# alu.net
KiCad netlist of a schematic drawn in EAGLE
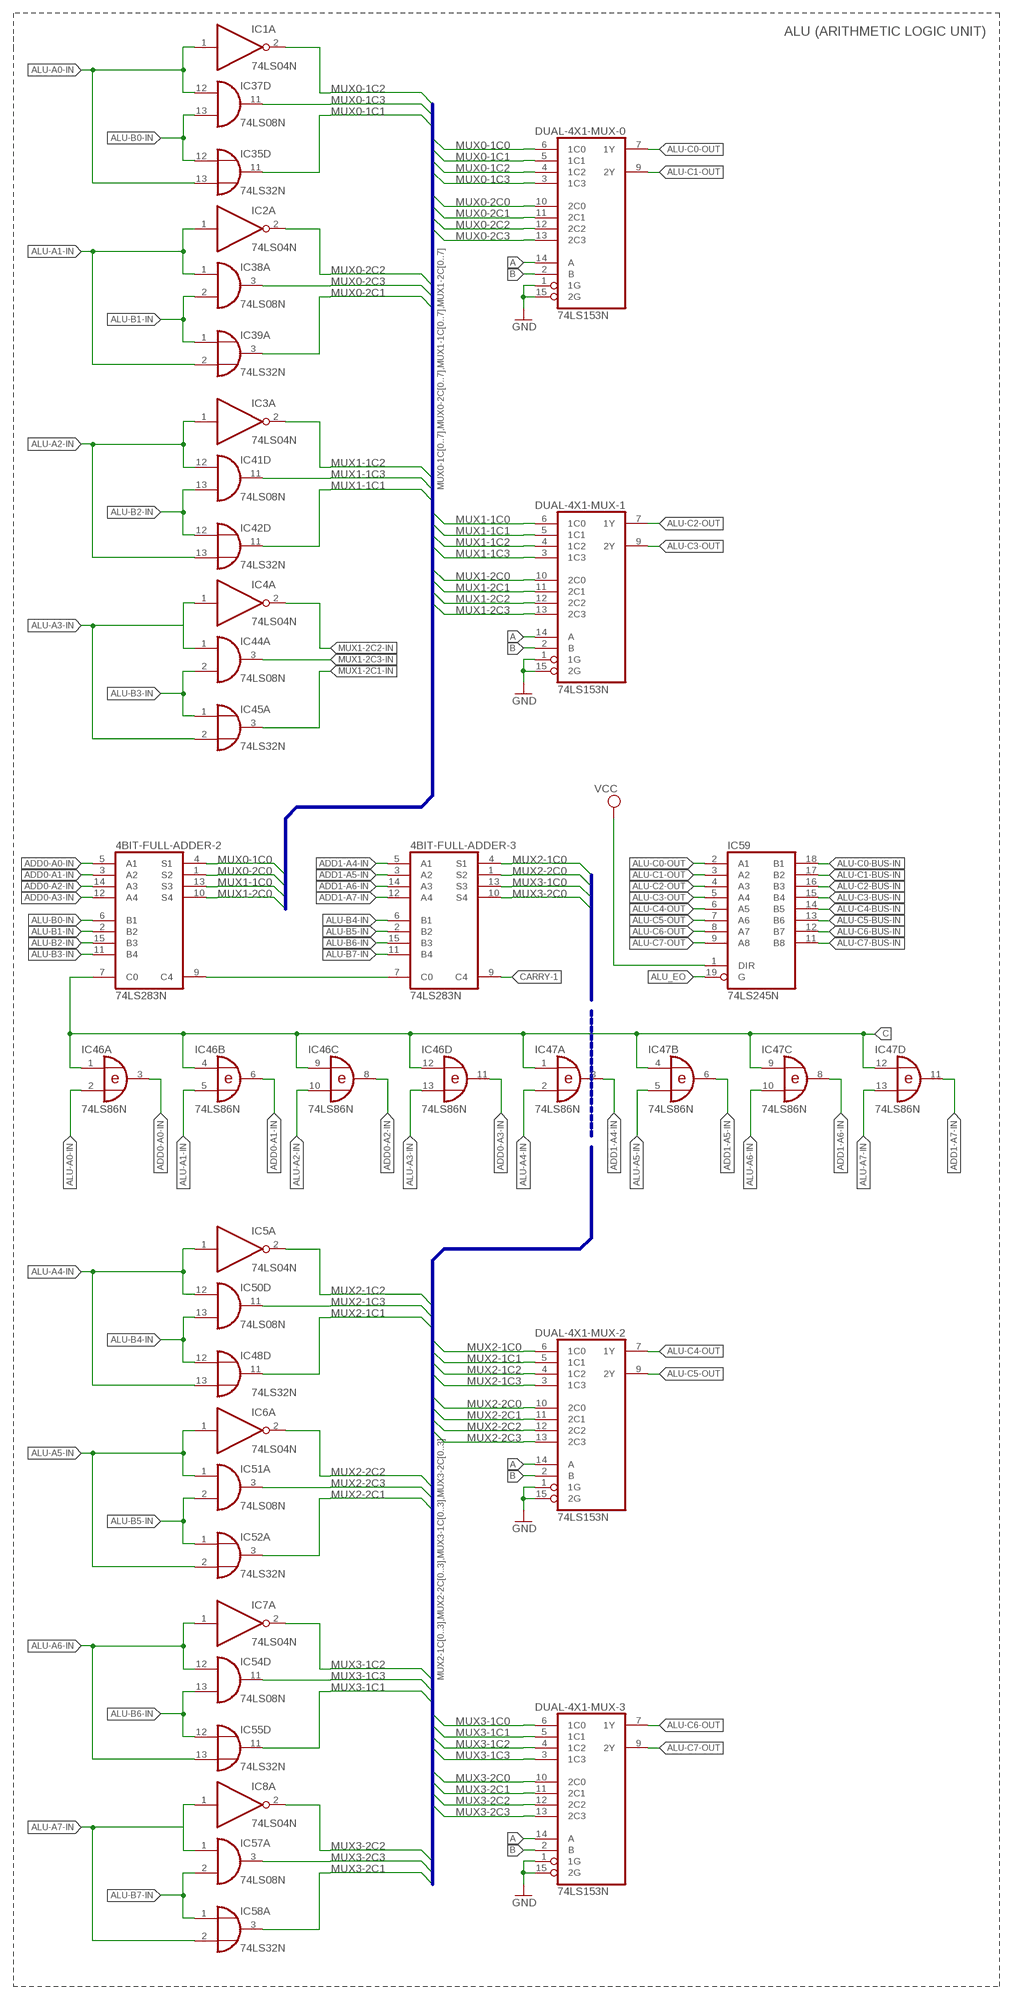
[diagram p0: schematic, sheet 1]

(export (version "E")
  (design (tool "Eeschema 10.0.6"))
  (components
    (comp (ref "4BIT-FULL-ADDER-2")
      (value "74LS283N")
      (footprint "eagle-import:DIL16")
      (libsource (lib "eagle-import") (part "74283NLS"))
    )
    (comp (ref "4BIT-FULL-ADDER-3")
      (value "74LS283N")
      (footprint "eagle-import:DIL16")
      (libsource (lib "eagle-import") (part "74283NLS"))
    )
    (comp (ref "DUAL-4X1-MUX-0")
      (value "74LS153N")
      (footprint "eagle-import:DIL16")
      (libsource (lib "eagle-import") (part "74153NLS"))
    )
    (comp (ref "DUAL-4X1-MUX-1")
      (value "74LS153N")
      (footprint "eagle-import:DIL16")
      (libsource (lib "eagle-import") (part "74153NLS"))
    )
    (comp (ref "DUAL-4X1-MUX-2")
      (value "74LS153N")
      (footprint "eagle-import:DIL16")
      (libsource (lib "eagle-import") (part "74153NLS"))
    )
    (comp (ref "DUAL-4X1-MUX-3")
      (value "74LS153N")
      (footprint "eagle-import:DIL16")
      (libsource (lib "eagle-import") (part "74153NLS"))
    )
    (comp (ref "IC1")
      (value "74LS04N")
      (footprint "eagle-import:DIL14")
      (libsource (lib "eagle-import") (part "7404NLS"))
    )
    (comp (ref "IC2")
      (value "74LS04N")
      (footprint "eagle-import:DIL14")
      (libsource (lib "eagle-import") (part "7404NLS"))
    )
    (comp (ref "IC3")
      (value "74LS04N")
      (footprint "eagle-import:DIL14")
      (libsource (lib "eagle-import") (part "7404NLS"))
    )
    (comp (ref "IC4")
      (value "74LS04N")
      (footprint "eagle-import:DIL14")
      (libsource (lib "eagle-import") (part "7404NLS"))
    )
    (comp (ref "IC5")
      (value "74LS04N")
      (footprint "eagle-import:DIL14")
      (libsource (lib "eagle-import") (part "7404NLS"))
    )
    (comp (ref "IC6")
      (value "74LS04N")
      (footprint "eagle-import:DIL14")
      (libsource (lib "eagle-import") (part "7404NLS"))
    )
    (comp (ref "IC7")
      (value "74LS04N")
      (footprint "eagle-import:DIL14")
      (libsource (lib "eagle-import") (part "7404NLS"))
    )
    (comp (ref "IC8")
      (value "74LS04N")
      (footprint "eagle-import:DIL14")
      (libsource (lib "eagle-import") (part "7404NLS"))
    )
    (comp (ref "IC35")
      (value "74LS32N")
      (footprint "eagle-import:DIL14")
      (libsource (lib "eagle-import") (part "7432NLS"))
    )
    (comp (ref "IC37")
      (value "74LS08N")
      (footprint "eagle-import:DIL14")
      (libsource (lib "eagle-import") (part "7408NLS"))
    )
    (comp (ref "IC38")
      (value "74LS08N")
      (footprint "eagle-import:DIL14")
      (libsource (lib "eagle-import") (part "7408NLS"))
    )
    (comp (ref "IC39")
      (value "74LS32N")
      (footprint "eagle-import:DIL14")
      (libsource (lib "eagle-import") (part "7432NLS"))
    )
    (comp (ref "IC41")
      (value "74LS08N")
      (footprint "eagle-import:DIL14")
      (libsource (lib "eagle-import") (part "7408NLS"))
    )
    (comp (ref "IC42")
      (value "74LS32N")
      (footprint "eagle-import:DIL14")
      (libsource (lib "eagle-import") (part "7432NLS"))
    )
    (comp (ref "IC44")
      (value "74LS08N")
      (footprint "eagle-import:DIL14")
      (libsource (lib "eagle-import") (part "7408NLS"))
    )
    (comp (ref "IC45")
      (value "74LS32N")
      (footprint "eagle-import:DIL14")
      (libsource (lib "eagle-import") (part "7432NLS"))
    )
    (comp (ref "IC46")
      (value "74LS86N")
      (footprint "eagle-import:DIL14")
      (libsource (lib "eagle-import") (part "7486NLS"))
    )
    (comp (ref "IC47")
      (value "74LS86N")
      (footprint "eagle-import:DIL14")
      (libsource (lib "eagle-import") (part "7486NLS"))
    )
    (comp (ref "IC48")
      (value "74LS32N")
      (footprint "eagle-import:DIL14")
      (libsource (lib "eagle-import") (part "7432NLS"))
    )
    (comp (ref "IC50")
      (value "74LS08N")
      (footprint "eagle-import:DIL14")
      (libsource (lib "eagle-import") (part "7408NLS"))
    )
    (comp (ref "IC51")
      (value "74LS08N")
      (footprint "eagle-import:DIL14")
      (libsource (lib "eagle-import") (part "7408NLS"))
    )
    (comp (ref "IC52")
      (value "74LS32N")
      (footprint "eagle-import:DIL14")
      (libsource (lib "eagle-import") (part "7432NLS"))
    )
    (comp (ref "IC54")
      (value "74LS08N")
      (footprint "eagle-import:DIL14")
      (libsource (lib "eagle-import") (part "7408NLS"))
    )
    (comp (ref "IC55")
      (value "74LS32N")
      (footprint "eagle-import:DIL14")
      (libsource (lib "eagle-import") (part "7432NLS"))
    )
    (comp (ref "IC57")
      (value "74LS08N")
      (footprint "eagle-import:DIL14")
      (libsource (lib "eagle-import") (part "7408NLS"))
    )
    (comp (ref "IC58")
      (value "74LS32N")
      (footprint "eagle-import:DIL14")
      (libsource (lib "eagle-import") (part "7432NLS"))
    )
    (comp (ref "IC59")
      (value "74LS245N")
      (footprint "eagle-import:DIL20")
      (libsource (lib "eagle-import") (part "74245NLS"))
    )
  )
  (nets
    (net (code "1") (name "/MUX0-1C0") (class "Default")
      (node (ref "4BIT-FULL-ADDER-2") (pin "4") (pinfunction "S1_4") (pintype "output"))
      (node (ref "DUAL-4X1-MUX-0") (pin "6") (pinfunction "1C0_6") (pintype "input"))
    )
    (net (code "2") (name "/MUX0-1C1") (class "Default")
      (node (ref "DUAL-4X1-MUX-0") (pin "5") (pinfunction "1C1_5") (pintype "input"))
      (node (ref "IC35") (pin "11") (pinfunction "O_11") (pintype "output"))
    )
    (net (code "3") (name "/MUX0-1C2") (class "Default")
      (node (ref "DUAL-4X1-MUX-0") (pin "4") (pinfunction "1C2_4") (pintype "input"))
      (node (ref "IC1") (pin "2") (pinfunction "O_2") (pintype "output"))
    )
    (net (code "4") (name "/MUX0-1C3") (class "Default")
      (node (ref "DUAL-4X1-MUX-0") (pin "3") (pinfunction "1C3_3") (pintype "input"))
      (node (ref "IC37") (pin "11") (pinfunction "O_11") (pintype "output"))
    )
    (net (code "5") (name "/MUX0-2C0") (class "Default")
      (node (ref "4BIT-FULL-ADDER-2") (pin "1") (pinfunction "S2_1") (pintype "output"))
      (node (ref "DUAL-4X1-MUX-0") (pin "10") (pinfunction "2C0_10") (pintype "input"))
    )
    (net (code "6") (name "/MUX0-2C1") (class "Default")
      (node (ref "DUAL-4X1-MUX-0") (pin "11") (pinfunction "2C1_11") (pintype "input"))
      (node (ref "IC39") (pin "3") (pinfunction "O_3") (pintype "output"))
    )
    (net (code "7") (name "/MUX0-2C2") (class "Default")
      (node (ref "DUAL-4X1-MUX-0") (pin "12") (pinfunction "2C2_12") (pintype "input"))
      (node (ref "IC2") (pin "2") (pinfunction "O_2") (pintype "output"))
    )
    (net (code "8") (name "/MUX0-2C3") (class "Default")
      (node (ref "DUAL-4X1-MUX-0") (pin "13") (pinfunction "2C3_13") (pintype "input"))
      (node (ref "IC38") (pin "3") (pinfunction "O_3") (pintype "output"))
    )
    (net (code "9") (name "/MUX1-1C0") (class "Default")
      (node (ref "4BIT-FULL-ADDER-2") (pin "13") (pinfunction "S3_13") (pintype "output"))
      (node (ref "DUAL-4X1-MUX-1") (pin "6") (pinfunction "1C0_6") (pintype "input"))
    )
    (net (code "10") (name "/MUX1-1C1") (class "Default")
      (node (ref "DUAL-4X1-MUX-1") (pin "5") (pinfunction "1C1_5") (pintype "input"))
      (node (ref "IC42") (pin "11") (pinfunction "O_11") (pintype "output"))
    )
    (net (code "11") (name "/MUX1-1C2") (class "Default")
      (node (ref "DUAL-4X1-MUX-1") (pin "4") (pinfunction "1C2_4") (pintype "input"))
      (node (ref "IC3") (pin "2") (pinfunction "O_2") (pintype "output"))
    )
    (net (code "12") (name "/MUX1-1C3") (class "Default")
      (node (ref "DUAL-4X1-MUX-1") (pin "3") (pinfunction "1C3_3") (pintype "input"))
      (node (ref "IC41") (pin "11") (pinfunction "O_11") (pintype "output"))
    )
    (net (code "13") (name "/MUX1-2C0") (class "Default")
      (node (ref "4BIT-FULL-ADDER-2") (pin "10") (pinfunction "S4_10") (pintype "output"))
      (node (ref "DUAL-4X1-MUX-1") (pin "10") (pinfunction "2C0_10") (pintype "input"))
    )
    (net (code "14") (name "/MUX1-2C1") (class "Default")
      (node (ref "DUAL-4X1-MUX-1") (pin "11") (pinfunction "2C1_11") (pintype "input"))
    )
    (net (code "15") (name "/MUX1-2C2") (class "Default")
      (node (ref "DUAL-4X1-MUX-1") (pin "12") (pinfunction "2C2_12") (pintype "input"))
    )
    (net (code "16") (name "/MUX1-2C3") (class "Default")
      (node (ref "DUAL-4X1-MUX-1") (pin "13") (pinfunction "2C3_13") (pintype "input"))
    )
    (net (code "17") (name "/MUX2-1C0") (class "Default")
      (node (ref "4BIT-FULL-ADDER-3") (pin "4") (pinfunction "S1_4") (pintype "output"))
      (node (ref "DUAL-4X1-MUX-2") (pin "6") (pinfunction "1C0_6") (pintype "input"))
    )
    (net (code "18") (name "/MUX2-1C1") (class "Default")
      (node (ref "DUAL-4X1-MUX-2") (pin "5") (pinfunction "1C1_5") (pintype "input"))
      (node (ref "IC48") (pin "11") (pinfunction "O_11") (pintype "output"))
    )
    (net (code "19") (name "/MUX2-1C2") (class "Default")
      (node (ref "DUAL-4X1-MUX-2") (pin "4") (pinfunction "1C2_4") (pintype "input"))
      (node (ref "IC5") (pin "2") (pinfunction "O_2") (pintype "output"))
    )
    (net (code "20") (name "/MUX2-1C3") (class "Default")
      (node (ref "DUAL-4X1-MUX-2") (pin "3") (pinfunction "1C3_3") (pintype "input"))
      (node (ref "IC50") (pin "11") (pinfunction "O_11") (pintype "output"))
    )
    (net (code "21") (name "/MUX2-2C0") (class "Default")
      (node (ref "4BIT-FULL-ADDER-3") (pin "1") (pinfunction "S2_1") (pintype "output"))
      (node (ref "DUAL-4X1-MUX-2") (pin "10") (pinfunction "2C0_10") (pintype "input"))
    )
    (net (code "22") (name "/MUX2-2C1") (class "Default")
      (node (ref "DUAL-4X1-MUX-2") (pin "11") (pinfunction "2C1_11") (pintype "input"))
      (node (ref "IC52") (pin "3") (pinfunction "O_3") (pintype "output"))
    )
    (net (code "23") (name "/MUX2-2C2") (class "Default")
      (node (ref "DUAL-4X1-MUX-2") (pin "12") (pinfunction "2C2_12") (pintype "input"))
      (node (ref "IC6") (pin "2") (pinfunction "O_2") (pintype "output"))
    )
    (net (code "24") (name "/MUX2-2C3") (class "Default")
      (node (ref "DUAL-4X1-MUX-2") (pin "13") (pinfunction "2C3_13") (pintype "input"))
      (node (ref "IC51") (pin "3") (pinfunction "O_3") (pintype "output"))
    )
    (net (code "25") (name "/MUX3-1C0") (class "Default")
      (node (ref "4BIT-FULL-ADDER-3") (pin "13") (pinfunction "S3_13") (pintype "output"))
      (node (ref "DUAL-4X1-MUX-3") (pin "6") (pinfunction "1C0_6") (pintype "input"))
    )
    (net (code "26") (name "/MUX3-1C1") (class "Default")
      (node (ref "DUAL-4X1-MUX-3") (pin "5") (pinfunction "1C1_5") (pintype "input"))
      (node (ref "IC55") (pin "11") (pinfunction "O_11") (pintype "output"))
    )
    (net (code "27") (name "/MUX3-1C2") (class "Default")
      (node (ref "DUAL-4X1-MUX-3") (pin "4") (pinfunction "1C2_4") (pintype "input"))
      (node (ref "IC7") (pin "2") (pinfunction "O_2") (pintype "output"))
    )
    (net (code "28") (name "/MUX3-1C3") (class "Default")
      (node (ref "DUAL-4X1-MUX-3") (pin "3") (pinfunction "1C3_3") (pintype "input"))
      (node (ref "IC54") (pin "11") (pinfunction "O_11") (pintype "output"))
    )
    (net (code "29") (name "/MUX3-2C0") (class "Default")
      (node (ref "4BIT-FULL-ADDER-3") (pin "10") (pinfunction "S4_10") (pintype "output"))
      (node (ref "DUAL-4X1-MUX-3") (pin "10") (pinfunction "2C0_10") (pintype "input"))
    )
    (net (code "30") (name "/MUX3-2C1") (class "Default")
      (node (ref "DUAL-4X1-MUX-3") (pin "11") (pinfunction "2C1_11") (pintype "input"))
      (node (ref "IC58") (pin "3") (pinfunction "O_3") (pintype "output"))
    )
    (net (code "31") (name "/MUX3-2C2") (class "Default")
      (node (ref "DUAL-4X1-MUX-3") (pin "12") (pinfunction "2C2_12") (pintype "input"))
      (node (ref "IC8") (pin "2") (pinfunction "O_2") (pintype "output"))
    )
    (net (code "32") (name "/MUX3-2C3") (class "Default")
      (node (ref "DUAL-4X1-MUX-3") (pin "13") (pinfunction "2C3_13") (pintype "input"))
      (node (ref "IC57") (pin "3") (pinfunction "O_3") (pintype "output"))
    )
    (net (code "35") (name "A") (class "Default")
      (node (ref "DUAL-4X1-MUX-0") (pin "14") (pinfunction "A_14") (pintype "input"))
      (node (ref "DUAL-4X1-MUX-1") (pin "14") (pinfunction "A_14") (pintype "input"))
      (node (ref "DUAL-4X1-MUX-2") (pin "14") (pinfunction "A_14") (pintype "input"))
      (node (ref "DUAL-4X1-MUX-3") (pin "14") (pinfunction "A_14") (pintype "input"))
    )
    (net (code "36") (name "ADD0-A0-IN") (class "Default")
      (node (ref "4BIT-FULL-ADDER-2") (pin "5") (pinfunction "A1_5") (pintype "input"))
      (node (ref "IC46") (pin "3") (pinfunction "O_3") (pintype "output"))
    )
    (net (code "37") (name "ADD0-A1-IN") (class "Default")
      (node (ref "4BIT-FULL-ADDER-2") (pin "3") (pinfunction "A2_3") (pintype "input"))
      (node (ref "IC46") (pin "6") (pinfunction "O_6") (pintype "output"))
    )
    (net (code "38") (name "ADD0-A2-IN") (class "Default")
      (node (ref "4BIT-FULL-ADDER-2") (pin "14") (pinfunction "A3_14") (pintype "input"))
      (node (ref "IC46") (pin "8") (pinfunction "O_8") (pintype "output"))
    )
    (net (code "39") (name "ADD0-A3-IN") (class "Default")
      (node (ref "4BIT-FULL-ADDER-2") (pin "12") (pinfunction "A4_12") (pintype "input"))
      (node (ref "IC46") (pin "11") (pinfunction "O_11") (pintype "output"))
    )
    (net (code "40") (name "ADD1-A4-IN") (class "Default")
      (node (ref "4BIT-FULL-ADDER-3") (pin "5") (pinfunction "A1_5") (pintype "input"))
      (node (ref "IC47") (pin "3") (pinfunction "O_3") (pintype "output"))
    )
    (net (code "41") (name "ADD1-A5-IN") (class "Default")
      (node (ref "4BIT-FULL-ADDER-3") (pin "3") (pinfunction "A2_3") (pintype "input"))
      (node (ref "IC47") (pin "6") (pinfunction "O_6") (pintype "output"))
    )
    (net (code "42") (name "ADD1-A6-IN") (class "Default")
      (node (ref "4BIT-FULL-ADDER-3") (pin "14") (pinfunction "A3_14") (pintype "input"))
      (node (ref "IC47") (pin "8") (pinfunction "O_8") (pintype "output"))
    )
    (net (code "43") (name "ADD1-A7-IN") (class "Default")
      (node (ref "4BIT-FULL-ADDER-3") (pin "12") (pinfunction "A4_12") (pintype "input"))
      (node (ref "IC47") (pin "11") (pinfunction "O_11") (pintype "output"))
    )
    (net (code "44") (name "ALU-A0-IN") (class "Default")
      (node (ref "IC1") (pin "1") (pinfunction "I_1") (pintype "input"))
      (node (ref "IC35") (pin "13") (pinfunction "I1_13") (pintype "input"))
      (node (ref "IC37") (pin "12") (pinfunction "I0_12") (pintype "input"))
      (node (ref "IC46") (pin "2") (pinfunction "I1_2") (pintype "input"))
    )
    (net (code "45") (name "ALU-A1-IN") (class "Default")
      (node (ref "IC2") (pin "1") (pinfunction "I_1") (pintype "input"))
      (node (ref "IC38") (pin "1") (pinfunction "I0_1") (pintype "input"))
      (node (ref "IC39") (pin "2") (pinfunction "I1_2") (pintype "input"))
      (node (ref "IC46") (pin "5") (pinfunction "I1_5") (pintype "input"))
    )
    (net (code "46") (name "ALU-A2-IN") (class "Default")
      (node (ref "IC3") (pin "1") (pinfunction "I_1") (pintype "input"))
      (node (ref "IC41") (pin "12") (pinfunction "I0_12") (pintype "input"))
      (node (ref "IC42") (pin "13") (pinfunction "I1_13") (pintype "input"))
      (node (ref "IC46") (pin "10") (pinfunction "I1_10") (pintype "input"))
    )
    (net (code "47") (name "ALU-A3-IN") (class "Default")
      (node (ref "IC4") (pin "1") (pinfunction "I_1") (pintype "input"))
      (node (ref "IC44") (pin "1") (pinfunction "I0_1") (pintype "input"))
      (node (ref "IC45") (pin "2") (pinfunction "I1_2") (pintype "input"))
      (node (ref "IC46") (pin "13") (pinfunction "I1_13") (pintype "input"))
    )
    (net (code "48") (name "ALU-A4-IN") (class "Default")
      (node (ref "IC47") (pin "2") (pinfunction "I1_2") (pintype "input"))
      (node (ref "IC48") (pin "13") (pinfunction "I1_13") (pintype "input"))
      (node (ref "IC5") (pin "1") (pinfunction "I_1") (pintype "input"))
      (node (ref "IC50") (pin "12") (pinfunction "I0_12") (pintype "input"))
    )
    (net (code "49") (name "ALU-A5-IN") (class "Default")
      (node (ref "IC47") (pin "5") (pinfunction "I1_5") (pintype "input"))
      (node (ref "IC51") (pin "1") (pinfunction "I0_1") (pintype "input"))
      (node (ref "IC52") (pin "2") (pinfunction "I1_2") (pintype "input"))
      (node (ref "IC6") (pin "1") (pinfunction "I_1") (pintype "input"))
    )
    (net (code "50") (name "ALU-A6-IN") (class "Default")
      (node (ref "IC47") (pin "10") (pinfunction "I1_10") (pintype "input"))
      (node (ref "IC54") (pin "12") (pinfunction "I0_12") (pintype "input"))
      (node (ref "IC55") (pin "13") (pinfunction "I1_13") (pintype "input"))
      (node (ref "IC7") (pin "1") (pinfunction "I_1") (pintype "input"))
    )
    (net (code "51") (name "ALU-A7-IN") (class "Default")
      (node (ref "IC47") (pin "13") (pinfunction "I1_13") (pintype "input"))
      (node (ref "IC57") (pin "1") (pinfunction "I0_1") (pintype "input"))
      (node (ref "IC58") (pin "2") (pinfunction "I1_2") (pintype "input"))
      (node (ref "IC8") (pin "1") (pinfunction "I_1") (pintype "input"))
    )
    (net (code "52") (name "ALU-B0-IN") (class "Default")
      (node (ref "4BIT-FULL-ADDER-2") (pin "6") (pinfunction "B1_6") (pintype "input"))
      (node (ref "IC35") (pin "12") (pinfunction "I0_12") (pintype "input"))
      (node (ref "IC37") (pin "13") (pinfunction "I1_13") (pintype "input"))
    )
    (net (code "53") (name "ALU-B1-IN") (class "Default")
      (node (ref "4BIT-FULL-ADDER-2") (pin "2") (pinfunction "B2_2") (pintype "input"))
      (node (ref "IC38") (pin "2") (pinfunction "I1_2") (pintype "input"))
      (node (ref "IC39") (pin "1") (pinfunction "I0_1") (pintype "input"))
    )
    (net (code "54") (name "ALU-B2-IN") (class "Default")
      (node (ref "4BIT-FULL-ADDER-2") (pin "15") (pinfunction "B3_15") (pintype "input"))
      (node (ref "IC41") (pin "13") (pinfunction "I1_13") (pintype "input"))
      (node (ref "IC42") (pin "12") (pinfunction "I0_12") (pintype "input"))
    )
    (net (code "55") (name "ALU-B3-IN") (class "Default")
      (node (ref "4BIT-FULL-ADDER-2") (pin "11") (pinfunction "B4_11") (pintype "input"))
      (node (ref "IC44") (pin "2") (pinfunction "I1_2") (pintype "input"))
      (node (ref "IC45") (pin "1") (pinfunction "I0_1") (pintype "input"))
    )
    (net (code "56") (name "ALU-B4-IN") (class "Default")
      (node (ref "4BIT-FULL-ADDER-3") (pin "6") (pinfunction "B1_6") (pintype "input"))
      (node (ref "IC48") (pin "12") (pinfunction "I0_12") (pintype "input"))
      (node (ref "IC50") (pin "13") (pinfunction "I1_13") (pintype "input"))
    )
    (net (code "57") (name "ALU-B5-IN") (class "Default")
      (node (ref "4BIT-FULL-ADDER-3") (pin "2") (pinfunction "B2_2") (pintype "input"))
      (node (ref "IC51") (pin "2") (pinfunction "I1_2") (pintype "input"))
      (node (ref "IC52") (pin "1") (pinfunction "I0_1") (pintype "input"))
    )
    (net (code "58") (name "ALU-B6-IN") (class "Default")
      (node (ref "4BIT-FULL-ADDER-3") (pin "15") (pinfunction "B3_15") (pintype "input"))
      (node (ref "IC54") (pin "13") (pinfunction "I1_13") (pintype "input"))
      (node (ref "IC55") (pin "12") (pinfunction "I0_12") (pintype "input"))
    )
    (net (code "59") (name "ALU-B7-IN") (class "Default")
      (node (ref "4BIT-FULL-ADDER-3") (pin "11") (pinfunction "B4_11") (pintype "input"))
      (node (ref "IC57") (pin "2") (pinfunction "I1_2") (pintype "input"))
      (node (ref "IC58") (pin "1") (pinfunction "I0_1") (pintype "input"))
    )
    (net (code "60") (name "ALU-C0-BUS-IN") (class "Default")
      (node (ref "IC59") (pin "18") (pinfunction "B1_18") (pintype "bidirectional"))
    )
    (net (code "61") (name "ALU-C0-OUT") (class "Default")
      (node (ref "DUAL-4X1-MUX-0") (pin "7") (pinfunction "1Y_7") (pintype "output"))
      (node (ref "IC59") (pin "2") (pinfunction "A1_2") (pintype "bidirectional"))
    )
    (net (code "62") (name "ALU-C1-BUS-IN") (class "Default")
      (node (ref "IC59") (pin "17") (pinfunction "B2_17") (pintype "bidirectional"))
    )
    (net (code "63") (name "ALU-C1-OUT") (class "Default")
      (node (ref "DUAL-4X1-MUX-0") (pin "9") (pinfunction "2Y_9") (pintype "output"))
      (node (ref "IC59") (pin "3") (pinfunction "A2_3") (pintype "bidirectional"))
    )
    (net (code "64") (name "ALU-C2-BUS-IN") (class "Default")
      (node (ref "IC59") (pin "16") (pinfunction "B3_16") (pintype "bidirectional"))
    )
    (net (code "65") (name "ALU-C2-OUT") (class "Default")
      (node (ref "DUAL-4X1-MUX-1") (pin "7") (pinfunction "1Y_7") (pintype "output"))
      (node (ref "IC59") (pin "4") (pinfunction "A3_4") (pintype "bidirectional"))
    )
    (net (code "66") (name "ALU-C3-BUS-IN") (class "Default")
      (node (ref "IC59") (pin "15") (pinfunction "B4_15") (pintype "bidirectional"))
    )
    (net (code "67") (name "ALU-C3-OUT") (class "Default")
      (node (ref "DUAL-4X1-MUX-1") (pin "9") (pinfunction "2Y_9") (pintype "output"))
      (node (ref "IC59") (pin "5") (pinfunction "A4_5") (pintype "bidirectional"))
    )
    (net (code "68") (name "ALU-C4-BUS-IN") (class "Default")
      (node (ref "IC59") (pin "14") (pinfunction "B5_14") (pintype "bidirectional"))
    )
    (net (code "69") (name "ALU-C4-OUT") (class "Default")
      (node (ref "DUAL-4X1-MUX-2") (pin "7") (pinfunction "1Y_7") (pintype "output"))
      (node (ref "IC59") (pin "6") (pinfunction "A5_6") (pintype "bidirectional"))
    )
    (net (code "70") (name "ALU-C5-BUS-IN") (class "Default")
      (node (ref "IC59") (pin "13") (pinfunction "B6_13") (pintype "bidirectional"))
    )
    (net (code "71") (name "ALU-C5-OUT") (class "Default")
      (node (ref "DUAL-4X1-MUX-2") (pin "9") (pinfunction "2Y_9") (pintype "output"))
      (node (ref "IC59") (pin "7") (pinfunction "A6_7") (pintype "bidirectional"))
    )
    (net (code "72") (name "ALU-C6-BUS-IN") (class "Default")
      (node (ref "IC59") (pin "12") (pinfunction "B7_12") (pintype "bidirectional"))
    )
    (net (code "73") (name "ALU-C6-OUT") (class "Default")
      (node (ref "DUAL-4X1-MUX-3") (pin "7") (pinfunction "1Y_7") (pintype "output"))
      (node (ref "IC59") (pin "8") (pinfunction "A7_8") (pintype "bidirectional"))
    )
    (net (code "74") (name "ALU-C7-BUS-IN") (class "Default")
      (node (ref "IC59") (pin "11") (pinfunction "B8_11") (pintype "bidirectional"))
    )
    (net (code "75") (name "ALU-C7-OUT") (class "Default")
      (node (ref "DUAL-4X1-MUX-3") (pin "9") (pinfunction "2Y_9") (pintype "output"))
      (node (ref "IC59") (pin "9") (pinfunction "A8_9") (pintype "bidirectional"))
    )
    (net (code "76") (name "ALU_EO") (class "Default")
      (node (ref "IC59") (pin "19") (pinfunction "G_19") (pintype "input"))
    )
    (net (code "77") (name "B") (class "Default")
      (node (ref "DUAL-4X1-MUX-0") (pin "2") (pinfunction "B_2") (pintype "input"))
      (node (ref "DUAL-4X1-MUX-1") (pin "2") (pinfunction "B_2") (pintype "input"))
      (node (ref "DUAL-4X1-MUX-2") (pin "2") (pinfunction "B_2") (pintype "input"))
      (node (ref "DUAL-4X1-MUX-3") (pin "2") (pinfunction "B_2") (pintype "input"))
    )
    (net (code "78") (name "C") (class "Default")
      (node (ref "4BIT-FULL-ADDER-2") (pin "7") (pinfunction "C0_7") (pintype "input"))
      (node (ref "IC46") (pin "1") (pinfunction "I0_1") (pintype "input"))
      (node (ref "IC46") (pin "12") (pinfunction "I0_12") (pintype "input"))
      (node (ref "IC46") (pin "4") (pinfunction "I0_4") (pintype "input"))
      (node (ref "IC46") (pin "9") (pinfunction "I0_9") (pintype "input"))
      (node (ref "IC47") (pin "1") (pinfunction "I0_1") (pintype "input"))
      (node (ref "IC47") (pin "12") (pinfunction "I0_12") (pintype "input"))
      (node (ref "IC47") (pin "4") (pinfunction "I0_4") (pintype "input"))
      (node (ref "IC47") (pin "9") (pinfunction "I0_9") (pintype "input"))
    )
    (net (code "79") (name "CARRY-1") (class "Default")
      (node (ref "4BIT-FULL-ADDER-3") (pin "9") (pinfunction "C4_9") (pintype "output"))
    )
    (net (code "80") (name "GND") (class "Default")
      (node (ref "DUAL-4X1-MUX-0") (pin "1") (pinfunction "1G_1") (pintype "input"))
      (node (ref "DUAL-4X1-MUX-0") (pin "15") (pinfunction "2G_15") (pintype "input"))
      (node (ref "DUAL-4X1-MUX-1") (pin "1") (pinfunction "1G_1") (pintype "input"))
      (node (ref "DUAL-4X1-MUX-1") (pin "15") (pinfunction "2G_15") (pintype "input"))
      (node (ref "DUAL-4X1-MUX-2") (pin "1") (pinfunction "1G_1") (pintype "input"))
      (node (ref "DUAL-4X1-MUX-2") (pin "15") (pinfunction "2G_15") (pintype "input"))
      (node (ref "DUAL-4X1-MUX-3") (pin "1") (pinfunction "1G_1") (pintype "input"))
      (node (ref "DUAL-4X1-MUX-3") (pin "15") (pinfunction "2G_15") (pintype "input"))
    )
    (net (code "81") (name "MUX1-2C1-IN") (class "Default")
      (node (ref "IC45") (pin "3") (pinfunction "O_3") (pintype "output"))
    )
    (net (code "82") (name "MUX1-2C2-IN") (class "Default")
      (node (ref "IC4") (pin "2") (pinfunction "O_2") (pintype "output"))
    )
    (net (code "83") (name "MUX1-2C3-IN") (class "Default")
      (node (ref "IC44") (pin "3") (pinfunction "O_3") (pintype "output"))
    )
    (net (code "84") (name "Net-(4BIT-FULL-ADDER-2A-C4)") (class "Default")
      (node (ref "4BIT-FULL-ADDER-2") (pin "9") (pinfunction "C4_9") (pintype "output"))
      (node (ref "4BIT-FULL-ADDER-3") (pin "7") (pinfunction "C0_7") (pintype "input"))
    )
    (net (code "85") (name "VCC") (class "Default")
      (node (ref "IC59") (pin "1") (pinfunction "DIR_1") (pintype "input"))
    )
  )
)
